# 03_ARM_A.net
KiCad netlist of a schematic drawn in Altium Designer
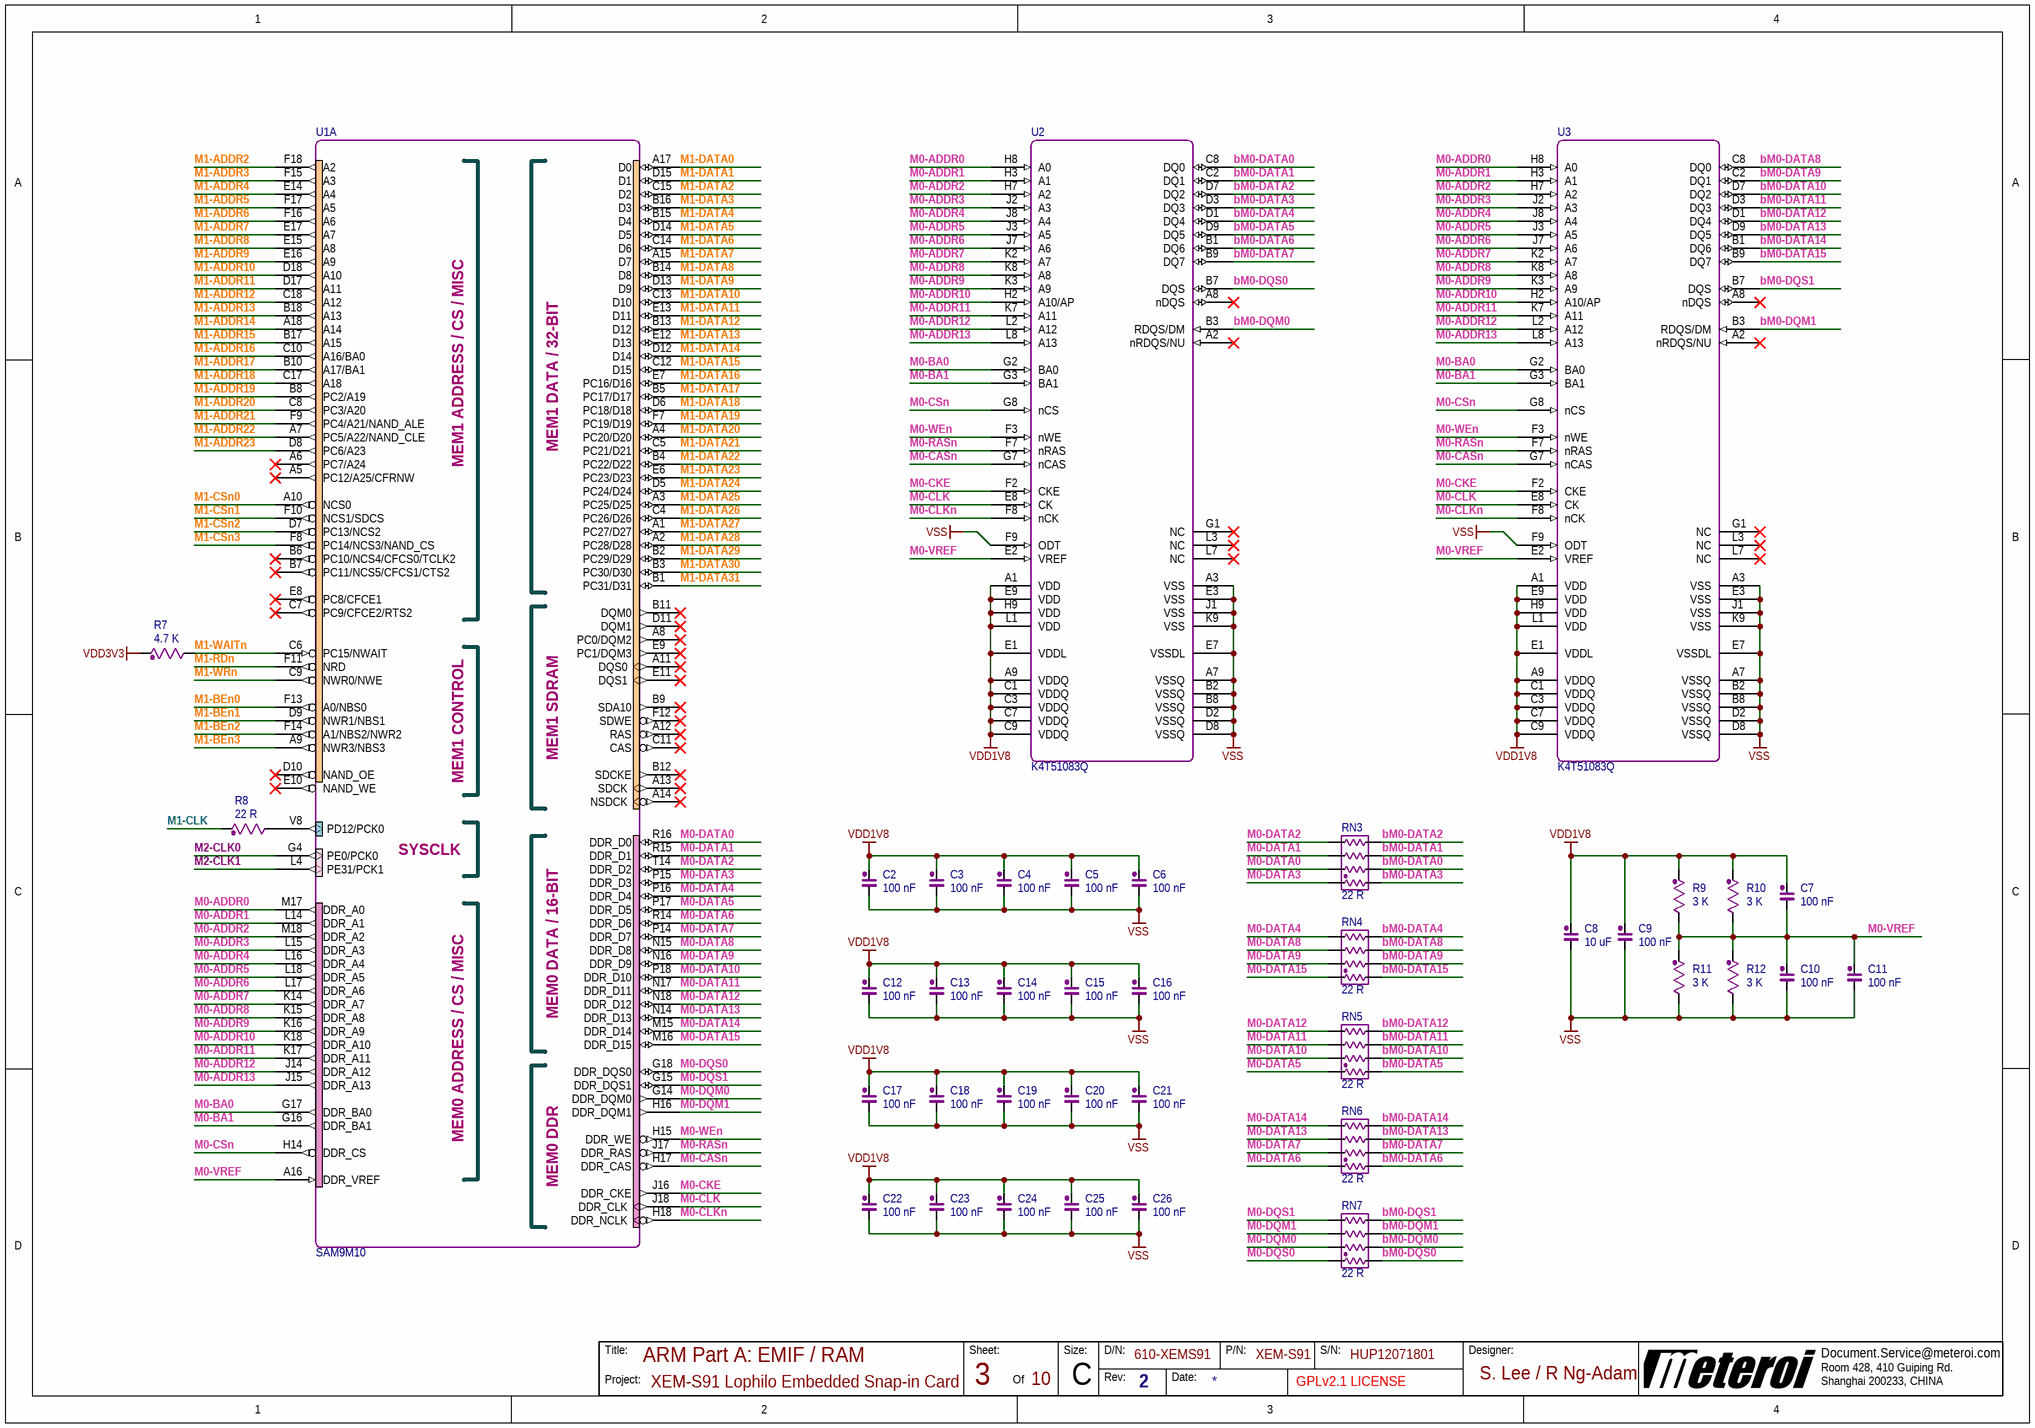
[diagram p0: 03_ARM_A.SchDoc]

(export (version "E")
  (design (tool "Eeschema 10.0.6"))
  (components
    (comp (ref "C2")
      (value "100 nF")
      (footprint "0402A1")
      (description "Normal Capacitor")
      (fields
        (field (name "PARTNUMBER") "0")
        (field (name "PUBLISHER") "Cowin")
        (field (name "DESIGNER") "shyul")
      )
      (libsource (lib "Basc_1_Passive") (part "CAP"))
    )
    (comp (ref "C3")
      (value "100 nF")
      (footprint "0402A1")
      (description "Normal Capacitor")
      (fields
        (field (name "PARTNUMBER") "0")
        (field (name "PUBLISHER") "Cowin")
        (field (name "DESIGNER") "shyul")
      )
      (libsource (lib "Basc_1_Passive") (part "CAP"))
    )
    (comp (ref "C4")
      (value "100 nF")
      (footprint "0402A1")
      (description "Normal Capacitor")
      (fields
        (field (name "PARTNUMBER") "0")
        (field (name "PUBLISHER") "Cowin")
        (field (name "DESIGNER") "shyul")
      )
      (libsource (lib "Basc_1_Passive") (part "CAP"))
    )
    (comp (ref "C5")
      (value "100 nF")
      (footprint "0402A1")
      (description "Normal Capacitor")
      (fields
        (field (name "PARTNUMBER") "0")
        (field (name "PUBLISHER") "Cowin")
        (field (name "DESIGNER") "shyul")
      )
      (libsource (lib "Basc_1_Passive") (part "CAP"))
    )
    (comp (ref "C6")
      (value "100 nF")
      (footprint "0402A1")
      (description "Normal Capacitor")
      (fields
        (field (name "PARTNUMBER") "0")
        (field (name "PUBLISHER") "Cowin")
        (field (name "DESIGNER") "shyul")
      )
      (libsource (lib "Basc_1_Passive") (part "CAP"))
    )
    (comp (ref "C7")
      (value "100 nF")
      (footprint "0402A1")
      (description "Normal Capacitor")
      (fields
        (field (name "PARTNUMBER") "0")
        (field (name "PUBLISHER") "Cowin")
        (field (name "DESIGNER") "shyul")
      )
      (libsource (lib "Basc_1_Passive") (part "CAP"))
    )
    (comp (ref "C8")
      (value "10 uF")
      (footprint "0603A1")
      (description "Normal Capacitor")
      (fields
        (field (name "PARTNUMBER") "0")
        (field (name "PUBLISHER") "Cowin")
        (field (name "DESIGNER") "shyul")
      )
      (libsource (lib "Basc_1_Passive") (part "CAP"))
    )
    (comp (ref "C9")
      (value "100 nF")
      (footprint "0402A1")
      (description "Normal Capacitor")
      (fields
        (field (name "PARTNUMBER") "0")
        (field (name "PUBLISHER") "Cowin")
        (field (name "DESIGNER") "shyul")
      )
      (libsource (lib "Basc_1_Passive") (part "CAP"))
    )
    (comp (ref "C10")
      (value "100 nF")
      (footprint "0402A1")
      (description "Normal Capacitor")
      (fields
        (field (name "PARTNUMBER") "0")
        (field (name "PUBLISHER") "Cowin")
        (field (name "DESIGNER") "shyul")
      )
      (libsource (lib "Basc_1_Passive") (part "CAP"))
    )
    (comp (ref "C11")
      (value "100 nF")
      (footprint "0402A1")
      (description "Normal Capacitor")
      (fields
        (field (name "PARTNUMBER") "0")
        (field (name "PUBLISHER") "Cowin")
        (field (name "DESIGNER") "shyul")
      )
      (libsource (lib "Basc_1_Passive") (part "CAP"))
    )
    (comp (ref "C12")
      (value "100 nF")
      (footprint "0402A1")
      (description "Normal Capacitor")
      (fields
        (field (name "PARTNUMBER") "0")
        (field (name "PUBLISHER") "Cowin")
        (field (name "DESIGNER") "shyul")
      )
      (libsource (lib "Basc_1_Passive") (part "CAP"))
    )
    (comp (ref "C13")
      (value "100 nF")
      (footprint "0402A1")
      (description "Normal Capacitor")
      (fields
        (field (name "PARTNUMBER") "0")
        (field (name "PUBLISHER") "Cowin")
        (field (name "DESIGNER") "shyul")
      )
      (libsource (lib "Basc_1_Passive") (part "CAP"))
    )
    (comp (ref "C14")
      (value "100 nF")
      (footprint "0402A1")
      (description "Normal Capacitor")
      (fields
        (field (name "PARTNUMBER") "0")
        (field (name "PUBLISHER") "Cowin")
        (field (name "DESIGNER") "shyul")
      )
      (libsource (lib "Basc_1_Passive") (part "CAP"))
    )
    (comp (ref "C15")
      (value "100 nF")
      (footprint "0402A1")
      (description "Normal Capacitor")
      (fields
        (field (name "PARTNUMBER") "0")
        (field (name "PUBLISHER") "Cowin")
        (field (name "DESIGNER") "shyul")
      )
      (libsource (lib "Basc_1_Passive") (part "CAP"))
    )
    (comp (ref "C16")
      (value "100 nF")
      (footprint "0402A1")
      (description "Normal Capacitor")
      (fields
        (field (name "PARTNUMBER") "0")
        (field (name "PUBLISHER") "Cowin")
        (field (name "DESIGNER") "shyul")
      )
      (libsource (lib "Basc_1_Passive") (part "CAP"))
    )
    (comp (ref "C17")
      (value "100 nF")
      (footprint "0402A1")
      (description "Normal Capacitor")
      (fields
        (field (name "PARTNUMBER") "0")
        (field (name "PUBLISHER") "Cowin")
        (field (name "DESIGNER") "shyul")
      )
      (libsource (lib "Basc_1_Passive") (part "CAP"))
    )
    (comp (ref "C18")
      (value "100 nF")
      (footprint "0402A1")
      (description "Normal Capacitor")
      (fields
        (field (name "PARTNUMBER") "0")
        (field (name "PUBLISHER") "Cowin")
        (field (name "DESIGNER") "shyul")
      )
      (libsource (lib "Basc_1_Passive") (part "CAP"))
    )
    (comp (ref "C19")
      (value "100 nF")
      (footprint "0402A1")
      (description "Normal Capacitor")
      (fields
        (field (name "PARTNUMBER") "0")
        (field (name "PUBLISHER") "Cowin")
        (field (name "DESIGNER") "shyul")
      )
      (libsource (lib "Basc_1_Passive") (part "CAP"))
    )
    (comp (ref "C20")
      (value "100 nF")
      (footprint "0402A1")
      (description "Normal Capacitor")
      (fields
        (field (name "PARTNUMBER") "0")
        (field (name "PUBLISHER") "Cowin")
        (field (name "DESIGNER") "shyul")
      )
      (libsource (lib "Basc_1_Passive") (part "CAP"))
    )
    (comp (ref "C21")
      (value "100 nF")
      (footprint "0402A1")
      (description "Normal Capacitor")
      (fields
        (field (name "PARTNUMBER") "0")
        (field (name "PUBLISHER") "Cowin")
        (field (name "DESIGNER") "shyul")
      )
      (libsource (lib "Basc_1_Passive") (part "CAP"))
    )
    (comp (ref "C22")
      (value "100 nF")
      (footprint "0402A1")
      (description "Normal Capacitor")
      (fields
        (field (name "PARTNUMBER") "0")
        (field (name "PUBLISHER") "Cowin")
        (field (name "DESIGNER") "shyul")
      )
      (libsource (lib "Basc_1_Passive") (part "CAP"))
    )
    (comp (ref "C23")
      (value "100 nF")
      (footprint "0402A1")
      (description "Normal Capacitor")
      (fields
        (field (name "PARTNUMBER") "0")
        (field (name "PUBLISHER") "Cowin")
        (field (name "DESIGNER") "shyul")
      )
      (libsource (lib "Basc_1_Passive") (part "CAP"))
    )
    (comp (ref "C24")
      (value "100 nF")
      (footprint "0402A1")
      (description "Normal Capacitor")
      (fields
        (field (name "PARTNUMBER") "0")
        (field (name "PUBLISHER") "Cowin")
        (field (name "DESIGNER") "shyul")
      )
      (libsource (lib "Basc_1_Passive") (part "CAP"))
    )
    (comp (ref "C25")
      (value "100 nF")
      (footprint "0402A1")
      (description "Normal Capacitor")
      (fields
        (field (name "PARTNUMBER") "0")
        (field (name "PUBLISHER") "Cowin")
        (field (name "DESIGNER") "shyul")
      )
      (libsource (lib "Basc_1_Passive") (part "CAP"))
    )
    (comp (ref "C26")
      (value "100 nF")
      (footprint "0402A1")
      (description "Normal Capacitor")
      (fields
        (field (name "PARTNUMBER") "0")
        (field (name "PUBLISHER") "Cowin")
        (field (name "DESIGNER") "shyul")
      )
      (libsource (lib "Basc_1_Passive") (part "CAP"))
    )
    (comp (ref "R7")
      (value "4.7 K")
      (footprint "0402A2")
      (description "Normal Resistor")
      (fields
        (field (name "PARTNUMBER") "0")
        (field (name "DESIGNER") "shyul")
        (field (name "PUBLISHER") "Cowin")
      )
      (libsource (lib "Basc_1_Passive") (part "RES"))
    )
    (comp (ref "R8")
      (value "22 R")
      (footprint "0402A2")
      (description "Normal Resistor")
      (fields
        (field (name "PARTNUMBER") "0")
        (field (name "DESIGNER") "shyul")
        (field (name "PUBLISHER") "Cowin")
      )
      (libsource (lib "Basc_1_Passive") (part "RES"))
    )
    (comp (ref "R9")
      (value "3 K")
      (footprint "0402A2")
      (description "Normal Resistor")
      (fields
        (field (name "PARTNUMBER") "0")
        (field (name "DESIGNER") "shyul")
        (field (name "PUBLISHER") "Cowin")
      )
      (libsource (lib "Basc_1_Passive") (part "RES"))
    )
    (comp (ref "R10")
      (value "3 K")
      (footprint "0402A2")
      (description "Normal Resistor")
      (fields
        (field (name "PARTNUMBER") "0")
        (field (name "DESIGNER") "shyul")
        (field (name "PUBLISHER") "Cowin")
      )
      (libsource (lib "Basc_1_Passive") (part "RES"))
    )
    (comp (ref "R11")
      (value "3 K")
      (footprint "0402A2")
      (description "Normal Resistor")
      (fields
        (field (name "PARTNUMBER") "0")
        (field (name "DESIGNER") "shyul")
        (field (name "PUBLISHER") "Cowin")
      )
      (libsource (lib "Basc_1_Passive") (part "RES"))
    )
    (comp (ref "R12")
      (value "3 K")
      (footprint "0402A2")
      (description "Normal Resistor")
      (fields
        (field (name "PARTNUMBER") "0")
        (field (name "DESIGNER") "shyul")
        (field (name "PUBLISHER") "Cowin")
      )
      (libsource (lib "Basc_1_Passive") (part "RES"))
    )
    (comp (ref "RN3")
      (value "22 R")
      (footprint "0402PR4")
      (description "Resistor Array x4")
      (fields
        (field (name "PARTNUMBER") "YC124-JR-0722RL")
        (field (name "PUBLISHER") "Cowin")
        (field (name "DESIGNER") "shyul")
      )
      (libsource (lib "Basc_1_Passive") (part "RES_N4"))
    )
    (comp (ref "RN4")
      (value "22 R")
      (footprint "0402PR4")
      (description "Resistor Array x4")
      (fields
        (field (name "PARTNUMBER") "YC124-JR-0722RL")
        (field (name "PUBLISHER") "Cowin")
        (field (name "DESIGNER") "shyul")
      )
      (libsource (lib "Basc_1_Passive") (part "RES_N4"))
    )
    (comp (ref "RN5")
      (value "22 R")
      (footprint "0402PR4")
      (description "Resistor Array x4")
      (fields
        (field (name "PARTNUMBER") "YC124-JR-0722RL")
        (field (name "PUBLISHER") "Cowin")
        (field (name "DESIGNER") "shyul")
      )
      (libsource (lib "Basc_1_Passive") (part "RES_N4"))
    )
    (comp (ref "RN6")
      (value "22 R")
      (footprint "0402PR4")
      (description "Resistor Array x4")
      (fields
        (field (name "PARTNUMBER") "YC124-JR-0722RL")
        (field (name "PUBLISHER") "Cowin")
        (field (name "DESIGNER") "shyul")
      )
      (libsource (lib "Basc_1_Passive") (part "RES_N4"))
    )
    (comp (ref "RN7")
      (value "22 R")
      (footprint "0402PR4")
      (description "Resistor Array x4")
      (fields
        (field (name "PARTNUMBER") "YC124-JR-0722RL")
        (field (name "PUBLISHER") "Cowin")
        (field (name "DESIGNER") "shyul")
      )
      (libsource (lib "Basc_1_Passive") (part "RES_N4"))
    )
    (comp (ref "U1")
      (value "SAM9M10")
      (footprint "TFBGA-324")
      (description "SAM9M10 Embedded Processor")
      (fields
        (field (name "PARTNUMBER") "AT91SAM9M10-CU")
        (field (name "DESIGNER") "shyul")
        (field (name "PUBLISHER") "Cowin")
      )
      (libsource (lib "PCB_XEM-S91") (part "SAM9M10"))
    )
    (comp (ref "U2")
      (value "K4T51083Q")
      (footprint "FBGA-DDR-60")
      (description "K4T51083Q 64M x8 DDR2 SDRAM")
      (fields
        (field (name "PARTNUMBER") "K4T51083QI-BCE7")
        (field (name "DESIGNER") "shyul")
        (field (name "PUBLISHER") "Cowin")
      )
      (libsource (lib "PCB_XEM-S91") (part "K4T51083Q"))
    )
    (comp (ref "U3")
      (value "K4T51083Q")
      (footprint "FBGA-DDR-60")
      (description "K4T51083Q 64M x8 DDR2 SDRAM")
      (fields
        (field (name "PARTNUMBER") "K4T51083QI-BCE7")
        (field (name "DESIGNER") "shyul")
        (field (name "PUBLISHER") "Cowin")
      )
      (libsource (lib "PCB_XEM-S91") (part "K4T51083Q"))
    )
  )
  (nets
    (net (code "1") (name "/M0-ADDR0") (class "Default")
      (node (ref "U1") (pin "M17") (pinfunction "DDR_A0_M17") (pintype "output"))
      (node (ref "U2") (pin "H8") (pinfunction "A0_H8") (pintype "input"))
      (node (ref "U3") (pin "H8") (pinfunction "A0_H8") (pintype "input"))
    )
    (net (code "2") (name "/M0-ADDR1") (class "Default")
      (node (ref "U1") (pin "L14") (pinfunction "DDR_A1_L14") (pintype "output"))
      (node (ref "U2") (pin "H3") (pinfunction "A1_H3") (pintype "input"))
      (node (ref "U3") (pin "H3") (pinfunction "A1_H3") (pintype "input"))
    )
    (net (code "3") (name "/M0-ADDR2") (class "Default")
      (node (ref "U1") (pin "M18") (pinfunction "DDR_A2_M18") (pintype "output"))
      (node (ref "U2") (pin "H7") (pinfunction "A2_H7") (pintype "input"))
      (node (ref "U3") (pin "H7") (pinfunction "A2_H7") (pintype "input"))
    )
    (net (code "4") (name "/M0-ADDR3") (class "Default")
      (node (ref "U1") (pin "L15") (pinfunction "DDR_A3_L15") (pintype "output"))
      (node (ref "U2") (pin "J2") (pinfunction "A3_J2") (pintype "input"))
      (node (ref "U3") (pin "J2") (pinfunction "A3_J2") (pintype "input"))
    )
    (net (code "5") (name "/M0-ADDR4") (class "Default")
      (node (ref "U1") (pin "L16") (pinfunction "DDR_A4_L16") (pintype "output"))
      (node (ref "U2") (pin "J8") (pinfunction "A4_J8") (pintype "input"))
      (node (ref "U3") (pin "J8") (pinfunction "A4_J8") (pintype "input"))
    )
    (net (code "6") (name "/M0-ADDR5") (class "Default")
      (node (ref "U1") (pin "L18") (pinfunction "DDR_A5_L18") (pintype "output"))
      (node (ref "U2") (pin "J3") (pinfunction "A5_J3") (pintype "input"))
      (node (ref "U3") (pin "J3") (pinfunction "A5_J3") (pintype "input"))
    )
    (net (code "7") (name "/M0-ADDR6") (class "Default")
      (node (ref "U1") (pin "L17") (pinfunction "DDR_A6_L17") (pintype "output"))
      (node (ref "U2") (pin "J7") (pinfunction "A6_J7") (pintype "input"))
      (node (ref "U3") (pin "J7") (pinfunction "A6_J7") (pintype "input"))
    )
    (net (code "8") (name "/M0-ADDR7") (class "Default")
      (node (ref "U1") (pin "K14") (pinfunction "DDR_A7_K14") (pintype "output"))
      (node (ref "U2") (pin "K2") (pinfunction "A7_K2") (pintype "input"))
      (node (ref "U3") (pin "K2") (pinfunction "A7_K2") (pintype "input"))
    )
    (net (code "9") (name "/M0-ADDR8") (class "Default")
      (node (ref "U1") (pin "K15") (pinfunction "DDR_A8_K15") (pintype "output"))
      (node (ref "U2") (pin "K8") (pinfunction "A8_K8") (pintype "input"))
      (node (ref "U3") (pin "K8") (pinfunction "A8_K8") (pintype "input"))
    )
    (net (code "10") (name "/M0-ADDR9") (class "Default")
      (node (ref "U1") (pin "K16") (pinfunction "DDR_A9_K16") (pintype "output"))
      (node (ref "U2") (pin "K3") (pinfunction "A9_K3") (pintype "input"))
      (node (ref "U3") (pin "K3") (pinfunction "A9_K3") (pintype "input"))
    )
    (net (code "11") (name "/M0-ADDR10") (class "Default")
      (node (ref "U1") (pin "K18") (pinfunction "DDR_A10_K18") (pintype "output"))
      (node (ref "U2") (pin "H2") (pinfunction "A10/AP_H2") (pintype "input"))
      (node (ref "U3") (pin "H2") (pinfunction "A10/AP_H2") (pintype "input"))
    )
    (net (code "12") (name "/M0-ADDR11") (class "Default")
      (node (ref "U1") (pin "K17") (pinfunction "DDR_A11_K17") (pintype "output"))
      (node (ref "U2") (pin "K7") (pinfunction "A11_K7") (pintype "input"))
      (node (ref "U3") (pin "K7") (pinfunction "A11_K7") (pintype "input"))
    )
    (net (code "13") (name "/M0-ADDR12") (class "Default")
      (node (ref "U1") (pin "J14") (pinfunction "DDR_A12_J14") (pintype "output"))
      (node (ref "U2") (pin "L2") (pinfunction "A12_L2") (pintype "input"))
      (node (ref "U3") (pin "L2") (pinfunction "A12_L2") (pintype "input"))
    )
    (net (code "14") (name "/M0-ADDR13") (class "Default")
      (node (ref "U1") (pin "J15") (pinfunction "DDR_A13_J15") (pintype "output"))
      (node (ref "U2") (pin "L8") (pinfunction "A13_L8") (pintype "input"))
      (node (ref "U3") (pin "L8") (pinfunction "A13_L8") (pintype "input"))
    )
    (net (code "15") (name "/M0-BA0") (class "Default")
      (node (ref "U1") (pin "G17") (pinfunction "DDR_BA0_G17") (pintype "output"))
      (node (ref "U2") (pin "G2") (pinfunction "BA0_G2") (pintype "input"))
      (node (ref "U3") (pin "G2") (pinfunction "BA0_G2") (pintype "input"))
    )
    (net (code "16") (name "/M0-BA1") (class "Default")
      (node (ref "U1") (pin "G16") (pinfunction "DDR_BA1_G16") (pintype "output"))
      (node (ref "U2") (pin "G3") (pinfunction "BA1_G3") (pintype "input"))
      (node (ref "U3") (pin "G3") (pinfunction "BA1_G3") (pintype "input"))
    )
    (net (code "17") (name "/M0-CASn") (class "Default")
      (node (ref "U1") (pin "H17") (pinfunction "DDR_CAS_H17") (pintype "output"))
      (node (ref "U2") (pin "G7") (pinfunction "nCAS_G7") (pintype "input"))
      (node (ref "U3") (pin "G7") (pinfunction "nCAS_G7") (pintype "input"))
    )
    (net (code "18") (name "/M0-CKE") (class "Default")
      (node (ref "U1") (pin "J16") (pinfunction "DDR_CKE_J16") (pintype "output"))
      (node (ref "U2") (pin "F2") (pinfunction "CKE_F2") (pintype "input"))
      (node (ref "U3") (pin "F2") (pinfunction "CKE_F2") (pintype "input"))
    )
    (net (code "19") (name "/M0-CLK") (class "Default")
      (node (ref "U1") (pin "J18") (pinfunction "DDR_CLK_J18") (pintype "output"))
      (node (ref "U2") (pin "E8") (pinfunction "CK_E8") (pintype "input"))
      (node (ref "U3") (pin "E8") (pinfunction "CK_E8") (pintype "input"))
    )
    (net (code "20") (name "/M0-CLKn") (class "Default")
      (node (ref "U1") (pin "H18") (pinfunction "DDR_NCLK_H18") (pintype "output"))
      (node (ref "U2") (pin "F8") (pinfunction "nCK_F8") (pintype "input"))
      (node (ref "U3") (pin "F8") (pinfunction "nCK_F8") (pintype "input"))
    )
    (net (code "21") (name "/M0-CSn") (class "Default")
      (node (ref "U1") (pin "H14") (pinfunction "DDR_CS_H14") (pintype "output"))
      (node (ref "U2") (pin "G8") (pinfunction "nCS_G8") (pintype "input"))
      (node (ref "U3") (pin "G8") (pinfunction "nCS_G8") (pintype "input"))
    )
    (net (code "22") (name "/M0-DATA0") (class "Default")
      (node (ref "RN3") (pin "3") (pinfunction "3_3") (pintype "passive"))
      (node (ref "U1") (pin "R16") (pinfunction "DDR_D0_R16") (pintype "bidirectional"))
    )
    (net (code "23") (name "/M0-DATA1") (class "Default")
      (node (ref "RN3") (pin "5") (pinfunction "5_5") (pintype "passive"))
      (node (ref "U1") (pin "R15") (pinfunction "DDR_D1_R15") (pintype "bidirectional"))
    )
    (net (code "24") (name "/M0-DATA2") (class "Default")
      (node (ref "RN3") (pin "7") (pinfunction "7_7") (pintype "passive"))
      (node (ref "U1") (pin "T14") (pinfunction "DDR_D2_T14") (pintype "bidirectional"))
    )
    (net (code "25") (name "/M0-DATA3") (class "Default")
      (node (ref "RN3") (pin "1") (pinfunction "1_1") (pintype "passive"))
      (node (ref "U1") (pin "P15") (pinfunction "DDR_D3_P15") (pintype "bidirectional"))
    )
    (net (code "26") (name "/M0-DATA4") (class "Default")
      (node (ref "RN4") (pin "7") (pinfunction "7_7") (pintype "passive"))
      (node (ref "U1") (pin "P16") (pinfunction "DDR_D4_P16") (pintype "bidirectional"))
    )
    (net (code "27") (name "/M0-DATA5") (class "Default")
      (node (ref "RN5") (pin "1") (pinfunction "1_1") (pintype "passive"))
      (node (ref "U1") (pin "P17") (pinfunction "DDR_D5_P17") (pintype "bidirectional"))
    )
    (net (code "28") (name "/M0-DATA6") (class "Default")
      (node (ref "RN6") (pin "1") (pinfunction "1_1") (pintype "passive"))
      (node (ref "U1") (pin "R14") (pinfunction "DDR_D6_R14") (pintype "bidirectional"))
    )
    (net (code "29") (name "/M0-DATA7") (class "Default")
      (node (ref "RN6") (pin "3") (pinfunction "3_3") (pintype "passive"))
      (node (ref "U1") (pin "P14") (pinfunction "DDR_D7_P14") (pintype "bidirectional"))
    )
    (net (code "30") (name "/M0-DATA8") (class "Default")
      (node (ref "RN4") (pin "5") (pinfunction "5_5") (pintype "passive"))
      (node (ref "U1") (pin "N15") (pinfunction "DDR_D8_N15") (pintype "bidirectional"))
    )
    (net (code "31") (name "/M0-DATA9") (class "Default")
      (node (ref "RN4") (pin "3") (pinfunction "3_3") (pintype "passive"))
      (node (ref "U1") (pin "N16") (pinfunction "DDR_D9_N16") (pintype "bidirectional"))
    )
    (net (code "32") (name "/M0-DATA10") (class "Default")
      (node (ref "RN5") (pin "3") (pinfunction "3_3") (pintype "passive"))
      (node (ref "U1") (pin "P18") (pinfunction "DDR_D10_P18") (pintype "bidirectional"))
    )
    (net (code "33") (name "/M0-DATA11") (class "Default")
      (node (ref "RN5") (pin "5") (pinfunction "5_5") (pintype "passive"))
      (node (ref "U1") (pin "N17") (pinfunction "DDR_D11_N17") (pintype "bidirectional"))
    )
    (net (code "34") (name "/M0-DATA12") (class "Default")
      (node (ref "RN5") (pin "7") (pinfunction "7_7") (pintype "passive"))
      (node (ref "U1") (pin "N18") (pinfunction "DDR_D12_N18") (pintype "bidirectional"))
    )
    (net (code "35") (name "/M0-DATA13") (class "Default")
      (node (ref "RN6") (pin "5") (pinfunction "5_5") (pintype "passive"))
      (node (ref "U1") (pin "N14") (pinfunction "DDR_D13_N14") (pintype "bidirectional"))
    )
    (net (code "36") (name "/M0-DATA14") (class "Default")
      (node (ref "RN6") (pin "7") (pinfunction "7_7") (pintype "passive"))
      (node (ref "U1") (pin "M15") (pinfunction "DDR_D14_M15") (pintype "bidirectional"))
    )
    (net (code "37") (name "/M0-DATA15") (class "Default")
      (node (ref "RN4") (pin "1") (pinfunction "1_1") (pintype "passive"))
      (node (ref "U1") (pin "M16") (pinfunction "DDR_D15_M16") (pintype "bidirectional"))
    )
    (net (code "38") (name "/M0-DQM0") (class "Default")
      (node (ref "RN7") (pin "3") (pinfunction "3_3") (pintype "passive"))
      (node (ref "U1") (pin "G14") (pinfunction "DDR_DQM0_G14") (pintype "output"))
    )
    (net (code "39") (name "/M0-DQM1") (class "Default")
      (node (ref "RN7") (pin "5") (pinfunction "5_5") (pintype "passive"))
      (node (ref "U1") (pin "H16") (pinfunction "DDR_DQM1_H16") (pintype "output"))
    )
    (net (code "40") (name "/M0-DQS0") (class "Default")
      (node (ref "RN7") (pin "1") (pinfunction "1_1") (pintype "passive"))
      (node (ref "U1") (pin "G18") (pinfunction "DDR_DQS0_G18") (pintype "bidirectional"))
    )
    (net (code "41") (name "/M0-DQS1") (class "Default")
      (node (ref "RN7") (pin "7") (pinfunction "7_7") (pintype "passive"))
      (node (ref "U1") (pin "G15") (pinfunction "DDR_DQS1_G15") (pintype "bidirectional"))
    )
    (net (code "42") (name "/M0-RASn") (class "Default")
      (node (ref "U1") (pin "J17") (pinfunction "DDR_RAS_J17") (pintype "output"))
      (node (ref "U2") (pin "F7") (pinfunction "nRAS_F7") (pintype "input"))
      (node (ref "U3") (pin "F7") (pinfunction "nRAS_F7") (pintype "input"))
    )
    (net (code "43") (name "/M0-VREF") (class "Default")
      (node (ref "C10") (pin "2") (pinfunction "2_2") (pintype "passive"))
      (node (ref "C11") (pin "2") (pinfunction "2_2") (pintype "passive"))
      (node (ref "C7") (pin "1") (pinfunction "1_1") (pintype "passive"))
      (node (ref "R10") (pin "1") (pinfunction "1_1") (pintype "passive"))
      (node (ref "R11") (pin "2") (pinfunction "2_2") (pintype "passive"))
      (node (ref "R12") (pin "2") (pinfunction "2_2") (pintype "passive"))
      (node (ref "R9") (pin "1") (pinfunction "1_1") (pintype "passive"))
      (node (ref "U1") (pin "A16") (pinfunction "DDR_VREF_A16") (pintype "input"))
      (node (ref "U2") (pin "E2") (pinfunction "VREF_E2") (pintype "input"))
      (node (ref "U3") (pin "E2") (pinfunction "VREF_E2") (pintype "input"))
    )
    (net (code "44") (name "/M0-WEn") (class "Default")
      (node (ref "U1") (pin "H15") (pinfunction "DDR_WE_H15") (pintype "output"))
      (node (ref "U2") (pin "F3") (pinfunction "nWE_F3") (pintype "input"))
      (node (ref "U3") (pin "F3") (pinfunction "nWE_F3") (pintype "input"))
    )
    (net (code "45") (name "/M1-ADDR2") (class "Default")
      (node (ref "U1") (pin "F18") (pinfunction "A2_F18") (pintype "output"))
    )
    (net (code "46") (name "/M1-ADDR3") (class "Default")
      (node (ref "U1") (pin "F15") (pinfunction "A3_F15") (pintype "output"))
    )
    (net (code "47") (name "/M1-ADDR4") (class "Default")
      (node (ref "U1") (pin "E14") (pinfunction "A4_E14") (pintype "output"))
    )
    (net (code "48") (name "/M1-ADDR5") (class "Default")
      (node (ref "U1") (pin "F17") (pinfunction "A5_F17") (pintype "output"))
    )
    (net (code "49") (name "/M1-ADDR6") (class "Default")
      (node (ref "U1") (pin "F16") (pinfunction "A6_F16") (pintype "output"))
    )
    (net (code "50") (name "/M1-ADDR7") (class "Default")
      (node (ref "U1") (pin "E17") (pinfunction "A7_E17") (pintype "output"))
    )
    (net (code "51") (name "/M1-ADDR8") (class "Default")
      (node (ref "U1") (pin "E15") (pinfunction "A8_E15") (pintype "output"))
    )
    (net (code "52") (name "/M1-ADDR9") (class "Default")
      (node (ref "U1") (pin "E16") (pinfunction "A9_E16") (pintype "output"))
    )
    (net (code "53") (name "/M1-ADDR10") (class "Default")
      (node (ref "U1") (pin "D18") (pinfunction "A10_D18") (pintype "output"))
    )
    (net (code "54") (name "/M1-ADDR11") (class "Default")
      (node (ref "U1") (pin "D17") (pinfunction "A11_D17") (pintype "output"))
    )
    (net (code "55") (name "/M1-ADDR12") (class "Default")
      (node (ref "U1") (pin "C18") (pinfunction "A12_C18") (pintype "output"))
    )
    (net (code "56") (name "/M1-ADDR13") (class "Default")
      (node (ref "U1") (pin "B18") (pinfunction "A13_B18") (pintype "output"))
    )
    (net (code "57") (name "/M1-ADDR14") (class "Default")
      (node (ref "U1") (pin "A18") (pinfunction "A14_A18") (pintype "output"))
    )
    (net (code "58") (name "/M1-ADDR15") (class "Default")
      (node (ref "U1") (pin "B17") (pinfunction "A15_B17") (pintype "output"))
    )
    (net (code "59") (name "/M1-ADDR16") (class "Default")
      (node (ref "U1") (pin "C10") (pinfunction "A16/BA0_C10") (pintype "output"))
    )
    (net (code "60") (name "/M1-ADDR17") (class "Default")
      (node (ref "U1") (pin "B10") (pinfunction "A17/BA1_B10") (pintype "output"))
    )
    (net (code "61") (name "/M1-ADDR18") (class "Default")
      (node (ref "U1") (pin "C17") (pinfunction "A18_C17") (pintype "output"))
    )
    (net (code "62") (name "/M1-ADDR19") (class "Default")
      (node (ref "U1") (pin "B8") (pinfunction "PC2/A19_B8") (pintype "output"))
    )
    (net (code "63") (name "/M1-ADDR20") (class "Default")
      (node (ref "U1") (pin "C8") (pinfunction "PC3/A20_C8") (pintype "output"))
    )
    (net (code "64") (name "/M1-ADDR21") (class "Default")
      (node (ref "U1") (pin "F9") (pinfunction "PC4/A21/NAND_ALE_F9") (pintype "output"))
    )
    (net (code "65") (name "/M1-ADDR22") (class "Default")
      (node (ref "U1") (pin "A7") (pinfunction "PC5/A22/NAND_CLE_A7") (pintype "output"))
    )
    (net (code "66") (name "/M1-ADDR23") (class "Default")
      (node (ref "U1") (pin "D8") (pinfunction "PC6/A23_D8") (pintype "output"))
    )
    (net (code "67") (name "/M1-BEn0") (class "Default")
      (node (ref "U1") (pin "F13") (pinfunction "A0/NBS0_F13") (pintype "output"))
    )
    (net (code "68") (name "/M1-BEn1") (class "Default")
      (node (ref "U1") (pin "D9") (pinfunction "NWR1/NBS1_D9") (pintype "output"))
    )
    (net (code "69") (name "/M1-BEn2") (class "Default")
      (node (ref "U1") (pin "F14") (pinfunction "A1/NBS2/NWR2_F14") (pintype "output"))
    )
    (net (code "70") (name "/M1-BEn3") (class "Default")
      (node (ref "U1") (pin "A9") (pinfunction "NWR3/NBS3_A9") (pintype "output"))
    )
    (net (code "71") (name "/M1-CLK") (class "Default")
      (node (ref "R8") (pin "2") (pinfunction "2_2") (pintype "passive"))
    )
    (net (code "72") (name "/M1-CSn0") (class "Default")
      (node (ref "U1") (pin "A10") (pinfunction "NCS0_A10") (pintype "output"))
    )
    (net (code "73") (name "/M1-CSn1") (class "Default")
      (node (ref "U1") (pin "F10") (pinfunction "NCS1/SDCS_F10") (pintype "output"))
    )
    (net (code "74") (name "/M1-CSn2") (class "Default")
      (node (ref "U1") (pin "D7") (pinfunction "PC13/NCS2_D7") (pintype "output"))
    )
    (net (code "75") (name "/M1-CSn3") (class "Default")
      (node (ref "U1") (pin "F8") (pinfunction "PC14/NCS3/NAND_CS_F8") (pintype "output"))
    )
    (net (code "76") (name "/M1-DATA0") (class "Default")
      (node (ref "U1") (pin "A17") (pinfunction "D0_A17") (pintype "bidirectional"))
    )
    (net (code "77") (name "/M1-DATA1") (class "Default")
      (node (ref "U1") (pin "D15") (pinfunction "D1_D15") (pintype "bidirectional"))
    )
    (net (code "78") (name "/M1-DATA2") (class "Default")
      (node (ref "U1") (pin "C15") (pinfunction "D2_C15") (pintype "bidirectional"))
    )
    (net (code "79") (name "/M1-DATA3") (class "Default")
      (node (ref "U1") (pin "B16") (pinfunction "D3_B16") (pintype "bidirectional"))
    )
    (net (code "80") (name "/M1-DATA4") (class "Default")
      (node (ref "U1") (pin "B15") (pinfunction "D4_B15") (pintype "bidirectional"))
    )
    (net (code "81") (name "/M1-DATA5") (class "Default")
      (node (ref "U1") (pin "D14") (pinfunction "D5_D14") (pintype "bidirectional"))
    )
    (net (code "82") (name "/M1-DATA6") (class "Default")
      (node (ref "U1") (pin "C14") (pinfunction "D6_C14") (pintype "bidirectional"))
    )
    (net (code "83") (name "/M1-DATA7") (class "Default")
      (node (ref "U1") (pin "A15") (pinfunction "D7_A15") (pintype "bidirectional"))
    )
    (net (code "84") (name "/M1-DATA8") (class "Default")
      (node (ref "U1") (pin "B14") (pinfunction "D8_B14") (pintype "bidirectional"))
    )
    (net (code "85") (name "/M1-DATA9") (class "Default")
      (node (ref "U1") (pin "D13") (pinfunction "D9_D13") (pintype "bidirectional"))
    )
    (net (code "86") (name "/M1-DATA10") (class "Default")
      (node (ref "U1") (pin "C13") (pinfunction "D10_C13") (pintype "bidirectional"))
    )
    (net (code "87") (name "/M1-DATA11") (class "Default")
      (node (ref "U1") (pin "E13") (pinfunction "D11_E13") (pintype "bidirectional"))
    )
    (net (code "88") (name "/M1-DATA12") (class "Default")
      (node (ref "U1") (pin "B13") (pinfunction "D12_B13") (pintype "bidirectional"))
    )
    (net (code "89") (name "/M1-DATA13") (class "Default")
      (node (ref "U1") (pin "E12") (pinfunction "D13_E12") (pintype "bidirectional"))
    )
    (net (code "90") (name "/M1-DATA14") (class "Default")
      (node (ref "U1") (pin "D12") (pinfunction "D14_D12") (pintype "bidirectional"))
    )
    (net (code "91") (name "/M1-DATA15") (class "Default")
      (node (ref "U1") (pin "C12") (pinfunction "D15_C12") (pintype "bidirectional"))
    )
    (net (code "92") (name "/M1-DATA16") (class "Default")
      (node (ref "U1") (pin "E7") (pinfunction "PC16/D16_E7") (pintype "bidirectional"))
    )
    (net (code "93") (name "/M1-DATA17") (class "Default")
      (node (ref "U1") (pin "B5") (pinfunction "PC17/D17_B5") (pintype "bidirectional"))
    )
    (net (code "94") (name "/M1-DATA18") (class "Default")
      (node (ref "U1") (pin "D6") (pinfunction "PC18/D18_D6") (pintype "bidirectional"))
    )
    (net (code "95") (name "/M1-DATA19") (class "Default")
      (node (ref "U1") (pin "F7") (pinfunction "PC19/D19_F7") (pintype "bidirectional"))
    )
    (net (code "96") (name "/M1-DATA20") (class "Default")
      (node (ref "U1") (pin "A4") (pinfunction "PC20/D20_A4") (pintype "bidirectional"))
    )
    (net (code "97") (name "/M1-DATA21") (class "Default")
      (node (ref "U1") (pin "C5") (pinfunction "PC21/D21_C5") (pintype "bidirectional"))
    )
    (net (code "98") (name "/M1-DATA22") (class "Default")
      (node (ref "U1") (pin "B4") (pinfunction "PC22/D22_B4") (pintype "bidirectional"))
    )
    (net (code "99") (name "/M1-DATA23") (class "Default")
      (node (ref "U1") (pin "E6") (pinfunction "PC23/D23_E6") (pintype "bidirectional"))
    )
    (net (code "100") (name "/M1-DATA24") (class "Default")
      (node (ref "U1") (pin "D5") (pinfunction "PC24/D24_D5") (pintype "bidirectional"))
    )
    (net (code "101") (name "/M1-DATA25") (class "Default")
      (node (ref "U1") (pin "A3") (pinfunction "PC25/D25_A3") (pintype "bidirectional"))
    )
    (net (code "102") (name "/M1-DATA26") (class "Default")
      (node (ref "U1") (pin "C4") (pinfunction "PC26/D26_C4") (pintype "bidirectional"))
    )
    (net (code "103") (name "/M1-DATA27") (class "Default")
      (node (ref "U1") (pin "A1") (pinfunction "PC27/D27_A1") (pintype "bidirectional"))
    )
    (net (code "104") (name "/M1-DATA28") (class "Default")
      (node (ref "U1") (pin "A2") (pinfunction "PC28/D28_A2") (pintype "bidirectional"))
    )
    (net (code "105") (name "/M1-DATA29") (class "Default")
      (node (ref "U1") (pin "B2") (pinfunction "PC29/D29_B2") (pintype "bidirectional"))
    )
    (net (code "106") (name "/M1-DATA30") (class "Default")
      (node (ref "U1") (pin "B3") (pinfunction "PC30/D30_B3") (pintype "bidirectional"))
    )
    (net (code "107") (name "/M1-DATA31") (class "Default")
      (node (ref "U1") (pin "B1") (pinfunction "PC31/D31_B1") (pintype "bidirectional"))
    )
    (net (code "108") (name "/M1-RDn") (class "Default")
      (node (ref "U1") (pin "F11") (pinfunction "NRD_F11") (pintype "output"))
    )
    (net (code "109") (name "/M1-WAITn") (class "Default")
      (node (ref "R7") (pin "1") (pinfunction "1_1") (pintype "passive"))
      (node (ref "U1") (pin "C6") (pinfunction "PC15/NWAIT_C6") (pintype "input"))
    )
    (net (code "110") (name "/M1-WRn") (class "Default")
      (node (ref "U1") (pin "C9") (pinfunction "NWR0/NWE_C9") (pintype "output"))
    )
    (net (code "111") (name "/M2-CLK0") (class "Default")
      (node (ref "U1") (pin "G4") (pinfunction "PE0/PCK0_G4") (pintype "output"))
    )
    (net (code "112") (name "/M2-CLK1") (class "Default")
      (node (ref "U1") (pin "L4") (pinfunction "PE31/PCK1_L4") (pintype "output"))
    )
    (net (code "113") (name "/bM0-DATA0") (class "Default")
      (node (ref "RN3") (pin "4") (pinfunction "4_4") (pintype "passive"))
      (node (ref "U2") (pin "C8") (pinfunction "DQ0_C8") (pintype "bidirectional"))
    )
    (net (code "114") (name "/bM0-DATA1") (class "Default")
      (node (ref "RN3") (pin "6") (pinfunction "6_6") (pintype "passive"))
      (node (ref "U2") (pin "C2") (pinfunction "DQ1_C2") (pintype "bidirectional"))
    )
    (net (code "115") (name "/bM0-DATA2") (class "Default")
      (node (ref "RN3") (pin "8") (pinfunction "8_8") (pintype "passive"))
      (node (ref "U2") (pin "D7") (pinfunction "DQ2_D7") (pintype "bidirectional"))
    )
    (net (code "116") (name "/bM0-DATA3") (class "Default")
      (node (ref "RN3") (pin "2") (pinfunction "2_2") (pintype "passive"))
      (node (ref "U2") (pin "D3") (pinfunction "DQ3_D3") (pintype "bidirectional"))
    )
    (net (code "117") (name "/bM0-DATA4") (class "Default")
      (node (ref "RN4") (pin "8") (pinfunction "8_8") (pintype "passive"))
      (node (ref "U2") (pin "D1") (pinfunction "DQ4_D1") (pintype "bidirectional"))
    )
    (net (code "118") (name "/bM0-DATA5") (class "Default")
      (node (ref "RN5") (pin "2") (pinfunction "2_2") (pintype "passive"))
      (node (ref "U2") (pin "D9") (pinfunction "DQ5_D9") (pintype "bidirectional"))
    )
    (net (code "119") (name "/bM0-DATA6") (class "Default")
      (node (ref "RN6") (pin "2") (pinfunction "2_2") (pintype "passive"))
      (node (ref "U2") (pin "B1") (pinfunction "DQ6_B1") (pintype "bidirectional"))
    )
    (net (code "120") (name "/bM0-DATA7") (class "Default")
      (node (ref "RN6") (pin "4") (pinfunction "4_4") (pintype "passive"))
      (node (ref "U2") (pin "B9") (pinfunction "DQ7_B9") (pintype "bidirectional"))
    )
    (net (code "121") (name "/bM0-DATA8") (class "Default")
      (node (ref "RN4") (pin "6") (pinfunction "6_6") (pintype "passive"))
      (node (ref "U3") (pin "C8") (pinfunction "DQ0_C8") (pintype "bidirectional"))
    )
    (net (code "122") (name "/bM0-DATA9") (class "Default")
      (node (ref "RN4") (pin "4") (pinfunction "4_4") (pintype "passive"))
      (node (ref "U3") (pin "C2") (pinfunction "DQ1_C2") (pintype "bidirectional"))
    )
    (net (code "123") (name "/bM0-DATA10") (class "Default")
      (node (ref "RN5") (pin "4") (pinfunction "4_4") (pintype "passive"))
      (node (ref "U3") (pin "D7") (pinfunction "DQ2_D7") (pintype "bidirectional"))
    )
    (net (code "124") (name "/bM0-DATA11") (class "Default")
      (node (ref "RN5") (pin "6") (pinfunction "6_6") (pintype "passive"))
      (node (ref "U3") (pin "D3") (pinfunction "DQ3_D3") (pintype "bidirectional"))
    )
    (net (code "125") (name "/bM0-DATA12") (class "Default")
      (node (ref "RN5") (pin "8") (pinfunction "8_8") (pintype "passive"))
      (node (ref "U3") (pin "D1") (pinfunction "DQ4_D1") (pintype "bidirectional"))
    )
    (net (code "126") (name "/bM0-DATA13") (class "Default")
      (node (ref "RN6") (pin "6") (pinfunction "6_6") (pintype "passive"))
      (node (ref "U3") (pin "D9") (pinfunction "DQ5_D9") (pintype "bidirectional"))
    )
    (net (code "127") (name "/bM0-DATA14") (class "Default")
      (node (ref "RN6") (pin "8") (pinfunction "8_8") (pintype "passive"))
      (node (ref "U3") (pin "B1") (pinfunction "DQ6_B1") (pintype "bidirectional"))
    )
    (net (code "128") (name "/bM0-DATA15") (class "Default")
      (node (ref "RN4") (pin "2") (pinfunction "2_2") (pintype "passive"))
      (node (ref "U3") (pin "B9") (pinfunction "DQ7_B9") (pintype "bidirectional"))
    )
    (net (code "129") (name "/bM0-DQM0") (class "Default")
      (node (ref "RN7") (pin "4") (pinfunction "4_4") (pintype "passive"))
      (node (ref "U2") (pin "B3") (pinfunction "RDQS/DM_B3") (pintype "input"))
    )
    (net (code "130") (name "/bM0-DQM1") (class "Default")
      (node (ref "RN7") (pin "6") (pinfunction "6_6") (pintype "passive"))
      (node (ref "U3") (pin "B3") (pinfunction "RDQS/DM_B3") (pintype "input"))
    )
    (net (code "131") (name "/bM0-DQS0") (class "Default")
      (node (ref "RN7") (pin "2") (pinfunction "2_2") (pintype "passive"))
      (node (ref "U2") (pin "B7") (pinfunction "DQS_B7") (pintype "bidirectional"))
    )
    (net (code "132") (name "/bM0-DQS1") (class "Default")
      (node (ref "RN7") (pin "8") (pinfunction "8_8") (pintype "passive"))
      (node (ref "U3") (pin "B7") (pinfunction "DQS_B7") (pintype "bidirectional"))
    )
    (net (code "133") (name "Net-(U1A-PD12{slash}PCK0)") (class "Default")
      (node (ref "R8") (pin "1") (pinfunction "1_1") (pintype "passive"))
      (node (ref "U1") (pin "V8") (pinfunction "PD12/PCK0_V8") (pintype "output"))
    )
    (net (code "134") (name "VDD1V8") (class "Default")
      (node (ref "C12") (pin "2") (pinfunction "2_2") (pintype "passive"))
      (node (ref "C13") (pin "2") (pinfunction "2_2") (pintype "passive"))
      (node (ref "C14") (pin "2") (pinfunction "2_2") (pintype "passive"))
      (node (ref "C15") (pin "2") (pinfunction "2_2") (pintype "passive"))
      (node (ref "C16") (pin "2") (pinfunction "2_2") (pintype "passive"))
      (node (ref "C17") (pin "2") (pinfunction "2_2") (pintype "passive"))
      (node (ref "C18") (pin "2") (pinfunction "2_2") (pintype "passive"))
      (node (ref "C19") (pin "2") (pinfunction "2_2") (pintype "passive"))
      (node (ref "C2") (pin "2") (pinfunction "2_2") (pintype "passive"))
      (node (ref "C20") (pin "2") (pinfunction "2_2") (pintype "passive"))
      (node (ref "C21") (pin "2") (pinfunction "2_2") (pintype "passive"))
      (node (ref "C22") (pin "2") (pinfunction "2_2") (pintype "passive"))
      (node (ref "C23") (pin "2") (pinfunction "2_2") (pintype "passive"))
      (node (ref "C24") (pin "2") (pinfunction "2_2") (pintype "passive"))
      (node (ref "C25") (pin "2") (pinfunction "2_2") (pintype "passive"))
      (node (ref "C26") (pin "2") (pinfunction "2_2") (pintype "passive"))
      (node (ref "C3") (pin "2") (pinfunction "2_2") (pintype "passive"))
      (node (ref "C4") (pin "2") (pinfunction "2_2") (pintype "passive"))
      (node (ref "C5") (pin "2") (pinfunction "2_2") (pintype "passive"))
      (node (ref "C6") (pin "2") (pinfunction "2_2") (pintype "passive"))
      (node (ref "C7") (pin "2") (pinfunction "2_2") (pintype "passive"))
      (node (ref "C8") (pin "2") (pinfunction "2_2") (pintype "passive"))
      (node (ref "C9") (pin "2") (pinfunction "2_2") (pintype "passive"))
      (node (ref "R10") (pin "2") (pinfunction "2_2") (pintype "passive"))
      (node (ref "R9") (pin "2") (pinfunction "2_2") (pintype "passive"))
      (node (ref "U2") (pin "A1") (pinfunction "VDD_A1") (pintype "passive"))
      (node (ref "U2") (pin "A9") (pinfunction "VDDQ_A9") (pintype "passive"))
      (node (ref "U2") (pin "C1") (pinfunction "VDDQ_C1") (pintype "passive"))
      (node (ref "U2") (pin "C3") (pinfunction "VDDQ_C3") (pintype "passive"))
      (node (ref "U2") (pin "C7") (pinfunction "VDDQ_C7") (pintype "passive"))
      (node (ref "U2") (pin "C9") (pinfunction "VDDQ_C9") (pintype "passive"))
      (node (ref "U2") (pin "E1") (pinfunction "VDDL_E1") (pintype "passive"))
      (node (ref "U2") (pin "E9") (pinfunction "VDD_E9") (pintype "passive"))
      (node (ref "U2") (pin "H9") (pinfunction "VDD_H9") (pintype "passive"))
      (node (ref "U2") (pin "L1") (pinfunction "VDD_L1") (pintype "passive"))
      (node (ref "U3") (pin "A1") (pinfunction "VDD_A1") (pintype "passive"))
      (node (ref "U3") (pin "A9") (pinfunction "VDDQ_A9") (pintype "passive"))
      (node (ref "U3") (pin "C1") (pinfunction "VDDQ_C1") (pintype "passive"))
      (node (ref "U3") (pin "C3") (pinfunction "VDDQ_C3") (pintype "passive"))
      (node (ref "U3") (pin "C7") (pinfunction "VDDQ_C7") (pintype "passive"))
      (node (ref "U3") (pin "C9") (pinfunction "VDDQ_C9") (pintype "passive"))
      (node (ref "U3") (pin "E1") (pinfunction "VDDL_E1") (pintype "passive"))
      (node (ref "U3") (pin "E9") (pinfunction "VDD_E9") (pintype "passive"))
      (node (ref "U3") (pin "H9") (pinfunction "VDD_H9") (pintype "passive"))
      (node (ref "U3") (pin "L1") (pinfunction "VDD_L1") (pintype "passive"))
    )
    (net (code "135") (name "VDD3V3") (class "Default")
      (node (ref "R7") (pin "2") (pinfunction "2_2") (pintype "passive"))
    )
    (net (code "136") (name "VSS") (class "Default")
      (node (ref "C10") (pin "1") (pinfunction "1_1") (pintype "passive"))
      (node (ref "C11") (pin "1") (pinfunction "1_1") (pintype "passive"))
      (node (ref "C12") (pin "1") (pinfunction "1_1") (pintype "passive"))
      (node (ref "C13") (pin "1") (pinfunction "1_1") (pintype "passive"))
      (node (ref "C14") (pin "1") (pinfunction "1_1") (pintype "passive"))
      (node (ref "C15") (pin "1") (pinfunction "1_1") (pintype "passive"))
      (node (ref "C16") (pin "1") (pinfunction "1_1") (pintype "passive"))
      (node (ref "C17") (pin "1") (pinfunction "1_1") (pintype "passive"))
      (node (ref "C18") (pin "1") (pinfunction "1_1") (pintype "passive"))
      (node (ref "C19") (pin "1") (pinfunction "1_1") (pintype "passive"))
      (node (ref "C2") (pin "1") (pinfunction "1_1") (pintype "passive"))
      (node (ref "C20") (pin "1") (pinfunction "1_1") (pintype "passive"))
      (node (ref "C21") (pin "1") (pinfunction "1_1") (pintype "passive"))
      (node (ref "C22") (pin "1") (pinfunction "1_1") (pintype "passive"))
      (node (ref "C23") (pin "1") (pinfunction "1_1") (pintype "passive"))
      (node (ref "C24") (pin "1") (pinfunction "1_1") (pintype "passive"))
      (node (ref "C25") (pin "1") (pinfunction "1_1") (pintype "passive"))
      (node (ref "C26") (pin "1") (pinfunction "1_1") (pintype "passive"))
      (node (ref "C3") (pin "1") (pinfunction "1_1") (pintype "passive"))
      (node (ref "C4") (pin "1") (pinfunction "1_1") (pintype "passive"))
      (node (ref "C5") (pin "1") (pinfunction "1_1") (pintype "passive"))
      (node (ref "C6") (pin "1") (pinfunction "1_1") (pintype "passive"))
      (node (ref "C8") (pin "1") (pinfunction "1_1") (pintype "passive"))
      (node (ref "C9") (pin "1") (pinfunction "1_1") (pintype "passive"))
      (node (ref "R11") (pin "1") (pinfunction "1_1") (pintype "passive"))
      (node (ref "R12") (pin "1") (pinfunction "1_1") (pintype "passive"))
      (node (ref "U2") (pin "A3") (pinfunction "VSS_A3") (pintype "passive"))
      (node (ref "U2") (pin "A7") (pinfunction "VSSQ_A7") (pintype "passive"))
      (node (ref "U2") (pin "B2") (pinfunction "VSSQ_B2") (pintype "passive"))
      (node (ref "U2") (pin "B8") (pinfunction "VSSQ_B8") (pintype "passive"))
      (node (ref "U2") (pin "D2") (pinfunction "VSSQ_D2") (pintype "passive"))
      (node (ref "U2") (pin "D8") (pinfunction "VSSQ_D8") (pintype "passive"))
      (node (ref "U2") (pin "E3") (pinfunction "VSS_E3") (pintype "passive"))
      (node (ref "U2") (pin "E7") (pinfunction "VSSDL_E7") (pintype "passive"))
      (node (ref "U2") (pin "F9") (pinfunction "ODT_F9") (pintype "input"))
      (node (ref "U2") (pin "J1") (pinfunction "VSS_J1") (pintype "passive"))
      (node (ref "U2") (pin "K9") (pinfunction "VSS_K9") (pintype "passive"))
      (node (ref "U3") (pin "A3") (pinfunction "VSS_A3") (pintype "passive"))
      (node (ref "U3") (pin "A7") (pinfunction "VSSQ_A7") (pintype "passive"))
      (node (ref "U3") (pin "B2") (pinfunction "VSSQ_B2") (pintype "passive"))
      (node (ref "U3") (pin "B8") (pinfunction "VSSQ_B8") (pintype "passive"))
      (node (ref "U3") (pin "D2") (pinfunction "VSSQ_D2") (pintype "passive"))
      (node (ref "U3") (pin "D8") (pinfunction "VSSQ_D8") (pintype "passive"))
      (node (ref "U3") (pin "E3") (pinfunction "VSS_E3") (pintype "passive"))
      (node (ref "U3") (pin "E7") (pinfunction "VSSDL_E7") (pintype "passive"))
      (node (ref "U3") (pin "F9") (pinfunction "ODT_F9") (pintype "input"))
      (node (ref "U3") (pin "J1") (pinfunction "VSS_J1") (pintype "passive"))
      (node (ref "U3") (pin "K9") (pinfunction "VSS_K9") (pintype "passive"))
    )
    (net (code "137") (name "unconnected-(U1A-CAS-PadC11)") (class "Default")
      (node (ref "U1") (pin "C11") (pinfunction "CAS_C11") (pintype "output+no_connect"))
    )
    (net (code "138") (name "unconnected-(U1A-DQM0-PadB11)") (class "Default")
      (node (ref "U1") (pin "B11") (pinfunction "DQM0_B11") (pintype "output+no_connect"))
    )
    (net (code "139") (name "unconnected-(U1A-DQM1-PadD11)") (class "Default")
      (node (ref "U1") (pin "D11") (pinfunction "DQM1_D11") (pintype "output+no_connect"))
    )
    (net (code "140") (name "unconnected-(U1A-DQS0-PadA11)") (class "Default")
      (node (ref "U1") (pin "A11") (pinfunction "DQS0_A11") (pintype "output+no_connect"))
    )
    (net (code "141") (name "unconnected-(U1A-DQS1-PadE11)") (class "Default")
      (node (ref "U1") (pin "E11") (pinfunction "DQS1_E11") (pintype "output+no_connect"))
    )
    (net (code "142") (name "unconnected-(U1A-NAND_OE-PadD10)") (class "Default")
      (node (ref "U1") (pin "D10") (pinfunction "NAND_OE_D10") (pintype "output+no_connect"))
    )
    (net (code "143") (name "unconnected-(U1A-NAND_WE-PadE10)") (class "Default")
      (node (ref "U1") (pin "E10") (pinfunction "NAND_WE_E10") (pintype "output+no_connect"))
    )
    (net (code "144") (name "unconnected-(U1A-NSDCK-PadA14)") (class "Default")
      (node (ref "U1") (pin "A14") (pinfunction "NSDCK_A14") (pintype "output+no_connect"))
    )
    (net (code "145") (name "unconnected-(U1A-PC0{slash}DQM2-PadA8)") (class "Default")
      (node (ref "U1") (pin "A8") (pinfunction "PC0/DQM2_A8") (pintype "output+no_connect"))
    )
    (net (code "146") (name "unconnected-(U1A-PC1{slash}DQM3-PadE9)") (class "Default")
      (node (ref "U1") (pin "E9") (pinfunction "PC1/DQM3_E9") (pintype "output+no_connect"))
    )
    (net (code "147") (name "unconnected-(U1A-PC7{slash}A24-PadA6)") (class "Default")
      (node (ref "U1") (pin "A6") (pinfunction "PC7/A24_A6") (pintype "output+no_connect"))
    )
    (net (code "148") (name "unconnected-(U1A-PC8{slash}CFCE1-PadE8)") (class "Default")
      (node (ref "U1") (pin "E8") (pinfunction "PC8/CFCE1_E8") (pintype "output+no_connect"))
    )
    (net (code "149") (name "unconnected-(U1A-PC9{slash}CFCE2{slash}RTS2-PadC7)") (class "Default")
      (node (ref "U1") (pin "C7") (pinfunction "PC9/CFCE2/RTS2_C7") (pintype "output+no_connect"))
    )
    (net (code "150") (name "unconnected-(U1A-PC10{slash}NCS4{slash}CFCS0{slash}TCLK2-PadB6)") (class "Default")
      (node (ref "U1") (pin "B6") (pinfunction "PC10/NCS4/CFCS0/TCLK2_B6") (pintype "output+no_connect"))
    )
    (net (code "151") (name "unconnected-(U1A-PC11{slash}NCS5{slash}CFCS1{slash}CTS2-PadB7)") (class "Default")
      (node (ref "U1") (pin "B7") (pinfunction "PC11/NCS5/CFCS1/CTS2_B7") (pintype "output+no_connect"))
    )
    (net (code "152") (name "unconnected-(U1A-PC12{slash}A25{slash}CFRNW-PadA5)") (class "Default")
      (node (ref "U1") (pin "A5") (pinfunction "PC12/A25/CFRNW_A5") (pintype "output+no_connect"))
    )
    (net (code "153") (name "unconnected-(U1A-RAS-PadA12)") (class "Default")
      (node (ref "U1") (pin "A12") (pinfunction "RAS_A12") (pintype "output+no_connect"))
    )
    (net (code "154") (name "unconnected-(U1A-SDA10-PadB9)") (class "Default")
      (node (ref "U1") (pin "B9") (pinfunction "SDA10_B9") (pintype "output+no_connect"))
    )
    (net (code "155") (name "unconnected-(U1A-SDCK-PadA13)") (class "Default")
      (node (ref "U1") (pin "A13") (pinfunction "SDCK_A13") (pintype "output+no_connect"))
    )
    (net (code "156") (name "unconnected-(U1A-SDCKE-PadB12)") (class "Default")
      (node (ref "U1") (pin "B12") (pinfunction "SDCKE_B12") (pintype "output+no_connect"))
    )
    (net (code "157") (name "unconnected-(U1A-SDWE-PadF12)") (class "Default")
      (node (ref "U1") (pin "F12") (pinfunction "SDWE_F12") (pintype "output+no_connect"))
    )
    (net (code "158") (name "unconnected-(U2-NC-PadG1)") (class "Default")
      (node (ref "U2") (pin "G1") (pinfunction "NC_G1") (pintype "passive+no_connect"))
    )
    (net (code "159") (name "unconnected-(U2-NC-PadL3)") (class "Default")
      (node (ref "U2") (pin "L3") (pinfunction "NC_L3") (pintype "passive+no_connect"))
    )
    (net (code "160") (name "unconnected-(U2-NC-PadL7)") (class "Default")
      (node (ref "U2") (pin "L7") (pinfunction "NC_L7") (pintype "passive+no_connect"))
    )
    (net (code "161") (name "unconnected-(U2-nDQS-PadA8)") (class "Default")
      (node (ref "U2") (pin "A8") (pinfunction "nDQS_A8") (pintype "bidirectional+no_connect"))
    )
    (net (code "162") (name "unconnected-(U2-nRDQS{slash}NU-PadA2)") (class "Default")
      (node (ref "U2") (pin "A2") (pinfunction "nRDQS/NU_A2") (pintype "input+no_connect"))
    )
    (net (code "163") (name "unconnected-(U3-NC-PadG1)") (class "Default")
      (node (ref "U3") (pin "G1") (pinfunction "NC_G1") (pintype "passive+no_connect"))
    )
    (net (code "164") (name "unconnected-(U3-NC-PadL3)") (class "Default")
      (node (ref "U3") (pin "L3") (pinfunction "NC_L3") (pintype "passive+no_connect"))
    )
    (net (code "165") (name "unconnected-(U3-NC-PadL7)") (class "Default")
      (node (ref "U3") (pin "L7") (pinfunction "NC_L7") (pintype "passive+no_connect"))
    )
    (net (code "166") (name "unconnected-(U3-nDQS-PadA8)") (class "Default")
      (node (ref "U3") (pin "A8") (pinfunction "nDQS_A8") (pintype "bidirectional+no_connect"))
    )
    (net (code "167") (name "unconnected-(U3-nRDQS{slash}NU-PadA2)") (class "Default")
      (node (ref "U3") (pin "A2") (pinfunction "nRDQS/NU_A2") (pintype "input+no_connect"))
    )
  )
)
